# MA_board_1.net
KiCad netlist of a schematic drawn in EAGLE
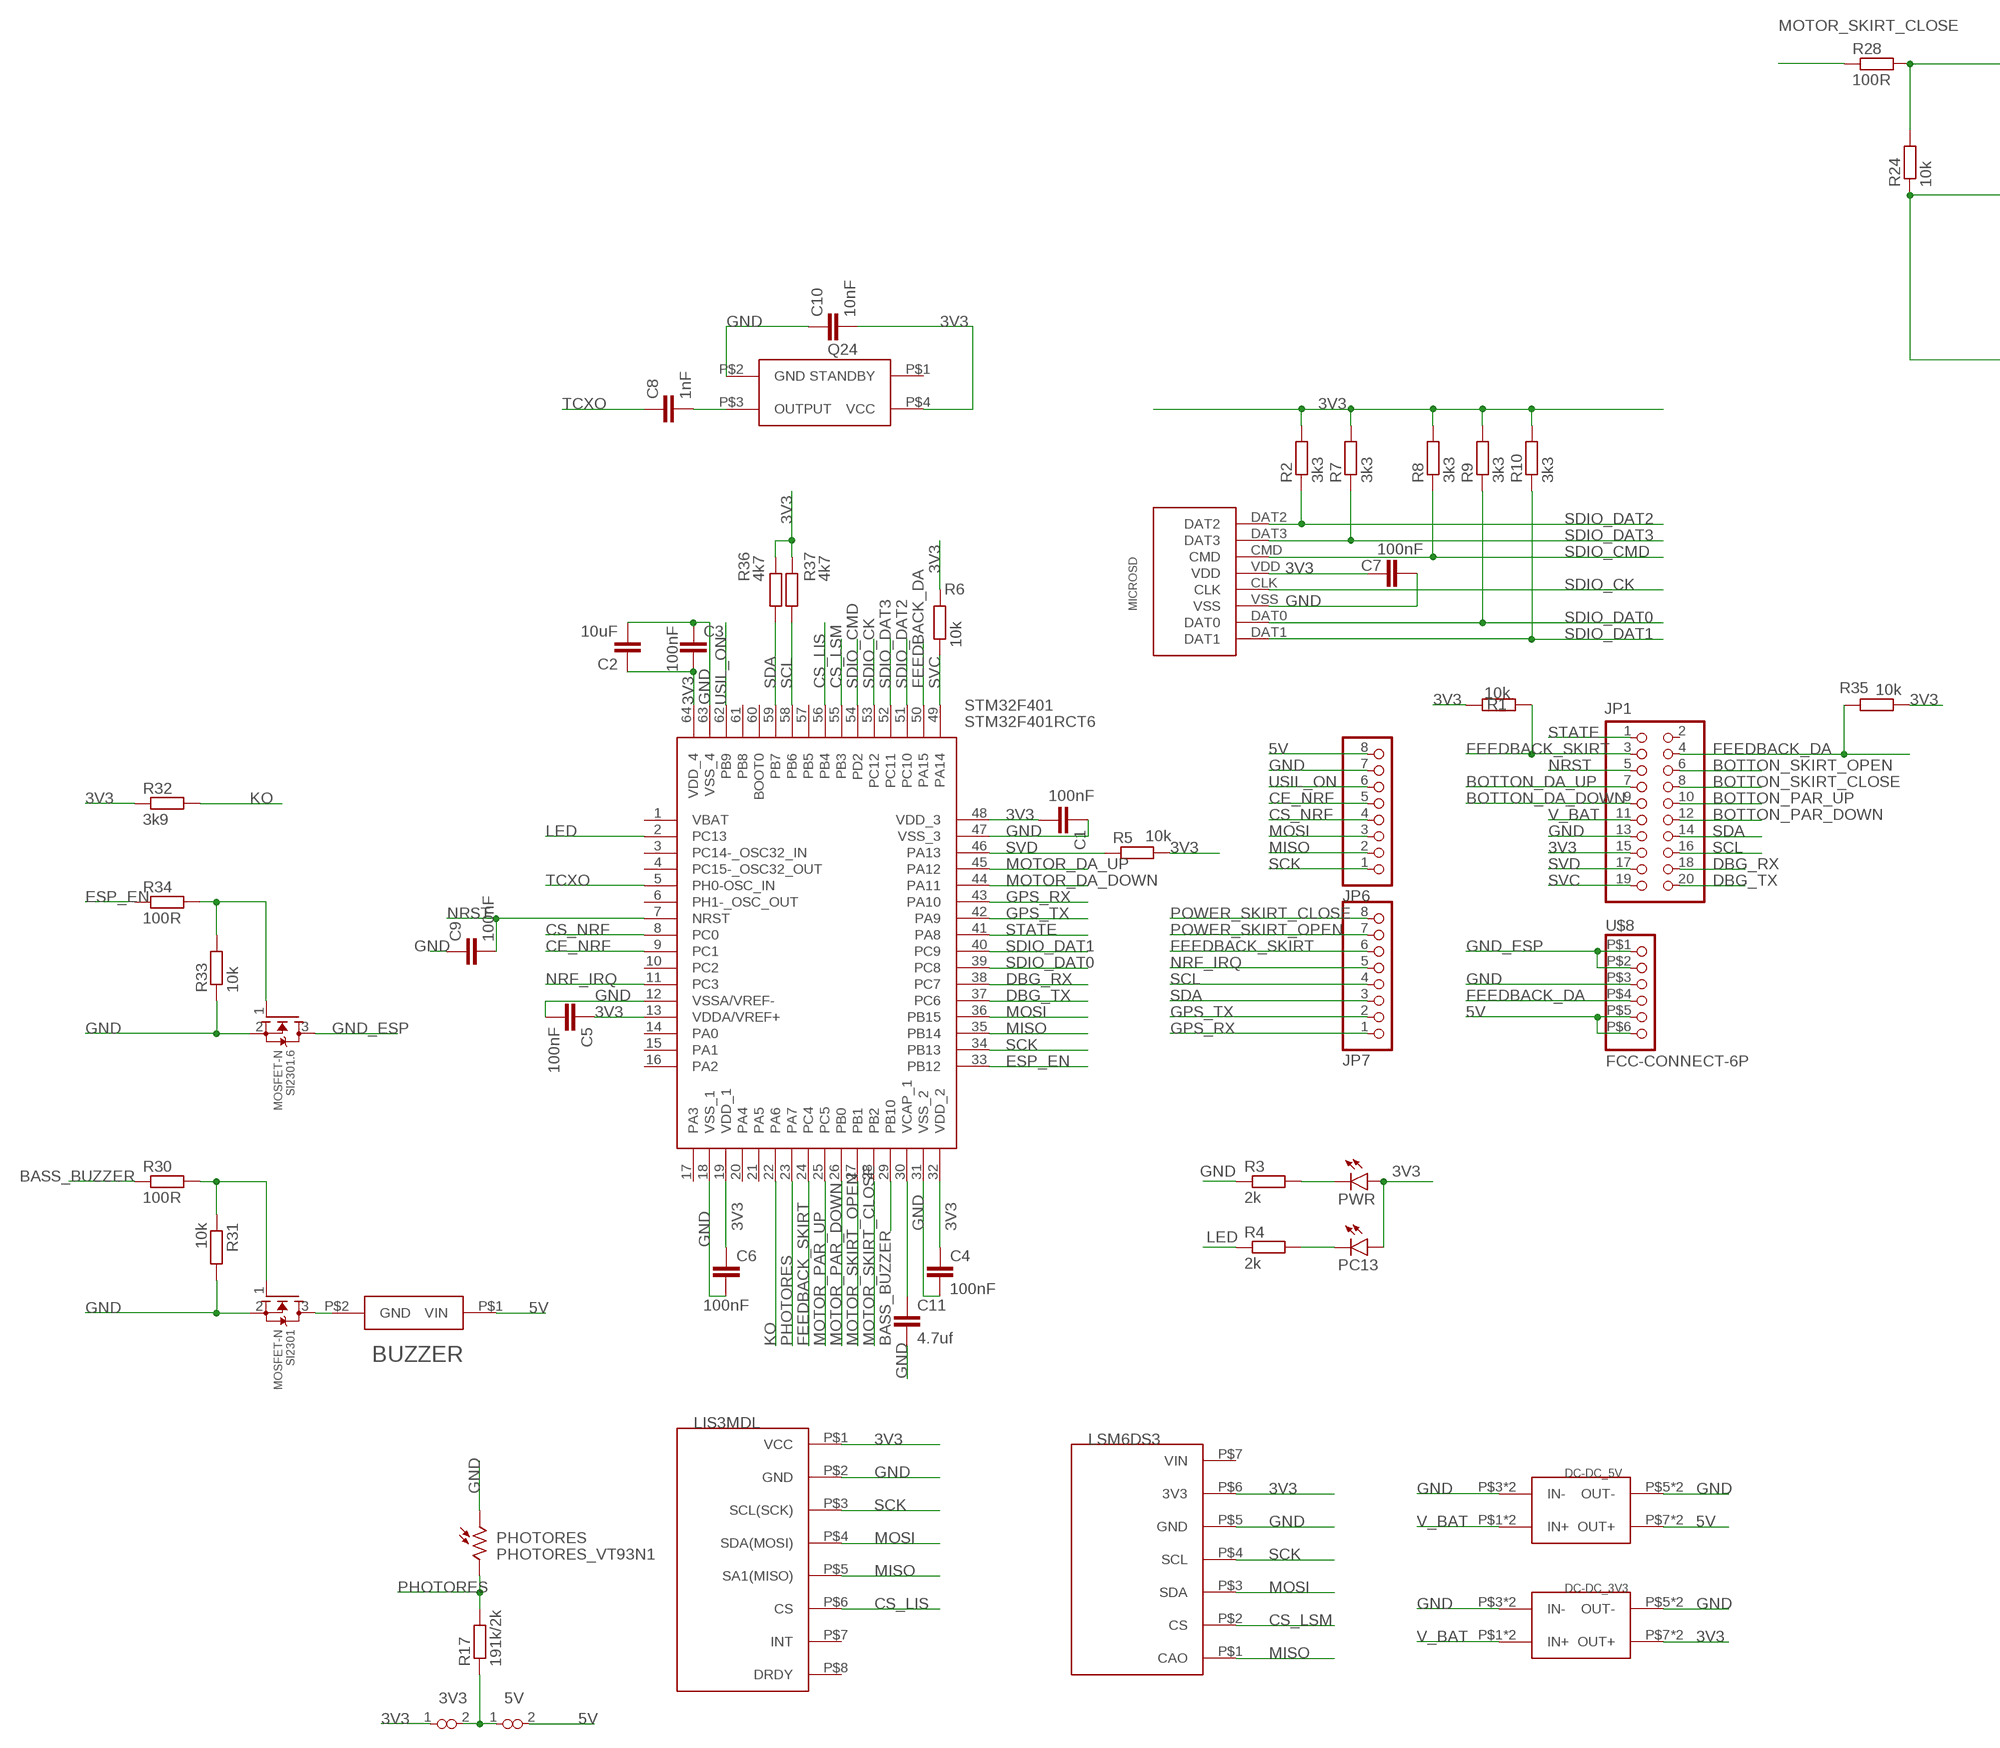
[diagram p0: schematic, sheet 1, part 1 of 2]
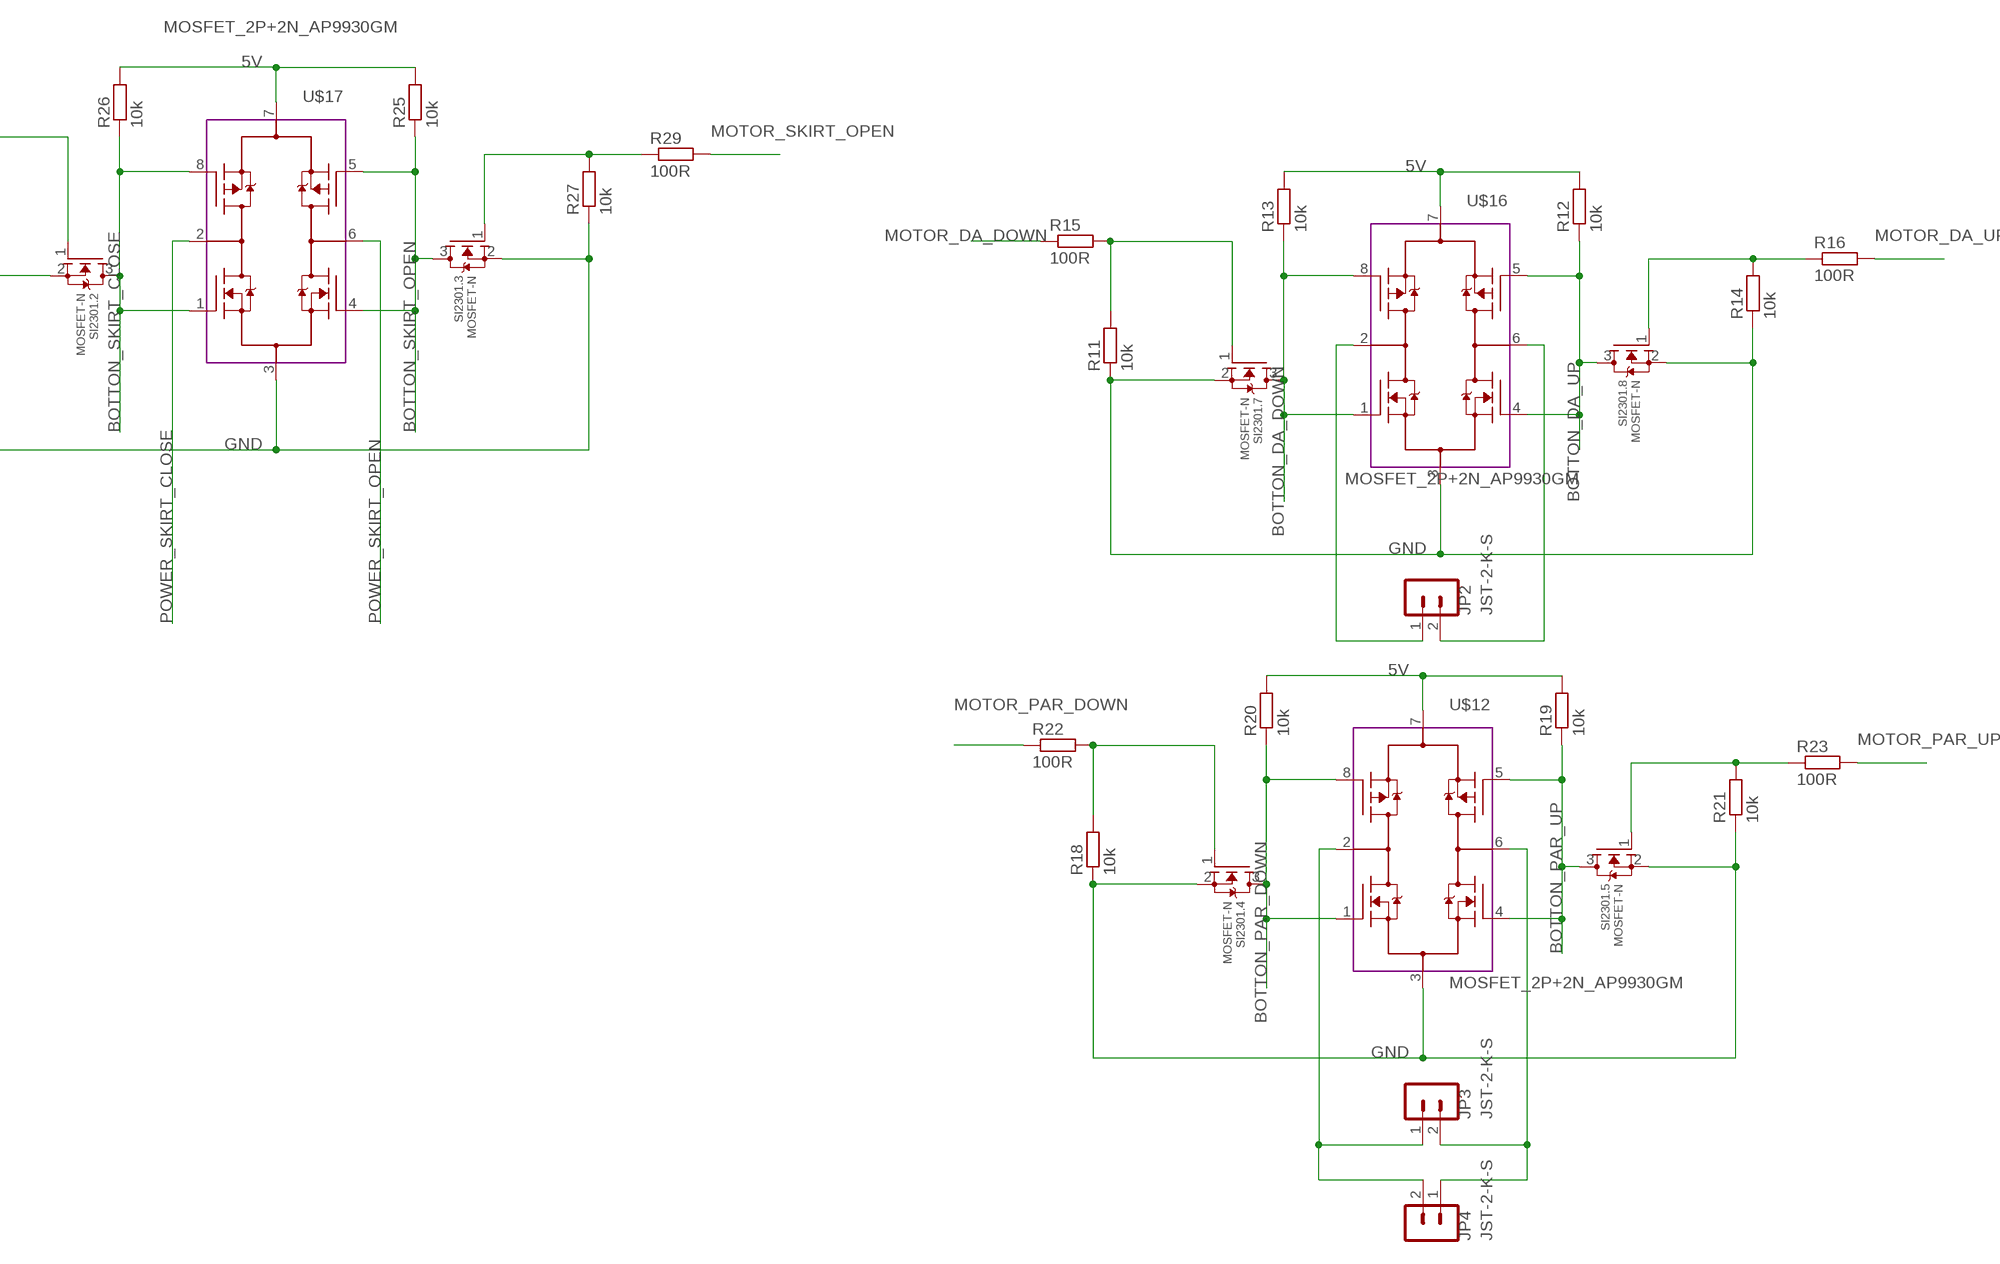
[diagram p1: schematic, sheet 1, part 2 of 2]

(export (version "E")
  (design (tool "Eeschema 10.0.6"))
  (components
    (comp (ref "3V3")
      (value "VIAS-CONNECT")
      (footprint "eagle-import:VIAS-CONNECT")
      (libsource (lib "eagle-import") (part "VIAS-CONNECT"))
    )
    (comp (ref "5V")
      (value "VIAS-CONNECT")
      (footprint "eagle-import:VIAS-CONNECT")
      (libsource (lib "eagle-import") (part "VIAS-CONNECT"))
    )
    (comp (ref "BUZZER")
      (value "BUZZERS8R6")
      (footprint "eagle-import:BUZZER-S8R12")
      (libsource (lib "eagle-import") (part "BUZZERS8R6"))
    )
    (comp (ref "C1")
      (value "100nF")
      (footprint "eagle-import:C0603")
      (libsource (lib "eagle-import") (part "C-EUC0603"))
    )
    (comp (ref "C2")
      (value "10uF")
      (footprint "eagle-import:C1206")
      (libsource (lib "eagle-import") (part "C-EUC1206"))
    )
    (comp (ref "C3")
      (value "100nF")
      (footprint "eagle-import:C0603")
      (libsource (lib "eagle-import") (part "C-EUC0603"))
    )
    (comp (ref "C4")
      (value "100nF")
      (footprint "eagle-import:C0603")
      (libsource (lib "eagle-import") (part "C-EUC0603"))
    )
    (comp (ref "C5")
      (value "100nF")
      (footprint "eagle-import:C0603")
      (libsource (lib "eagle-import") (part "C-EUC0603"))
    )
    (comp (ref "C6")
      (value "100nF")
      (footprint "eagle-import:C0603")
      (libsource (lib "eagle-import") (part "C-EUC0603"))
    )
    (comp (ref "C7")
      (value "100nF")
      (footprint "eagle-import:C0603")
      (libsource (lib "eagle-import") (part "C-EUC0603"))
    )
    (comp (ref "C8")
      (value "1nF")
      (footprint "eagle-import:C0603")
      (libsource (lib "eagle-import") (part "C-EUC0603"))
    )
    (comp (ref "C9")
      (value "100nF")
      (footprint "eagle-import:C0603")
      (libsource (lib "eagle-import") (part "C-EUC0603"))
    )
    (comp (ref "C10")
      (value "10nF")
      (footprint "eagle-import:C0603")
      (libsource (lib "eagle-import") (part "C-EUC0603"))
    )
    (comp (ref "C11")
      (value "4.7uf")
      (footprint "eagle-import:C0603")
      (libsource (lib "eagle-import") (part "C-EUC0603"))
    )
    (comp (ref "DC-DC_3V3")
      (value "MP1584-B")
      (footprint "eagle-import:MP1584-B")
      (libsource (lib "eagle-import") (part "MP1584-B"))
    )
    (comp (ref "DC-DC_5V")
      (value "MP1584-B")
      (footprint "eagle-import:MP1584-B")
      (libsource (lib "eagle-import") (part "MP1584-B"))
    )
    (comp (ref "JP1")
      (value "PINHD-2X10/90")
      (footprint "eagle-import:2X10_90")
      (libsource (lib "eagle-import") (part "PINHD-2X10/90"))
    )
    (comp (ref "JP2")
      (value "JST-2-K-S")
      (footprint "eagle-import:B2B-PH-K-S")
      (libsource (lib "eagle-import") (part "JST-2-K-S"))
    )
    (comp (ref "JP3")
      (value "JST-2-K-S")
      (footprint "eagle-import:B2B-PH-K-S")
      (libsource (lib "eagle-import") (part "JST-2-K-S"))
    )
    (comp (ref "JP4")
      (value "JST-2-K-S")
      (footprint "eagle-import:B2B-PH-K-S")
      (libsource (lib "eagle-import") (part "JST-2-K-S"))
    )
    (comp (ref "JP6")
      (value "PINHD-1X8-SHORT-PAD")
      (footprint "eagle-import:1X08")
      (libsource (lib "eagle-import") (part "PINHD-1X8-SHORT-PAD"))
    )
    (comp (ref "JP7")
      (value "PINHD-1X8-SHORT-PAD")
      (footprint "eagle-import:1X08")
      (libsource (lib "eagle-import") (part "PINHD-1X8-SHORT-PAD"))
    )
    (comp (ref "LIS3MDL")
      (value "LIS3MDL-CJMCUБез_отв._зеркальный")
      (footprint "eagle-import:LIS3MDL-CGMSU-NB2023")
      (libsource (lib "eagle-import") (part "LIS3MDL-CJMCUБез_отв._зеркальный"))
    )
    (comp (ref "LSM6DS3")
      (value "LSM6DS3-GY-NB2023")
      (footprint "eagle-import:LSM6DS3-GY-NB2023")
      (libsource (lib "eagle-import") (part "LSM6DS3-GY-NB2023"))
    )
    (comp (ref "MICROSD")
      (value "SD")
      (footprint "eagle-import:SD")
      (libsource (lib "eagle-import") (part "SD"))
    )
    (comp (ref "PC13")
      (value "LEDCHIPLED_0603")
      (footprint "eagle-import:CHIPLED_0603")
      (libsource (lib "eagle-import") (part "LEDCHIPLED_0603"))
    )
    (comp (ref "PHOTORES")
      (value "PHOTORES_VT93N1")
      (footprint "eagle-import:PHOTORES_VT93N1_SMD")
      (libsource (lib "eagle-import") (part "PHOTORES_VT93N1"))
    )
    (comp (ref "PWR")
      (value "LEDCHIPLED_0603")
      (footprint "eagle-import:CHIPLED_0603")
      (libsource (lib "eagle-import") (part "LEDCHIPLED_0603"))
    )
    (comp (ref "Q24")
      (value "Q24")
      (footprint "eagle-import:Q24")
      (libsource (lib "eagle-import") (part "Q24"))
    )
    (comp (ref "R1")
      (value "10k")
      (footprint "eagle-import:R0603")
      (libsource (lib "eagle-import") (part "R-EU_R0603"))
    )
    (comp (ref "R2")
      (value "3k3")
      (footprint "eagle-import:R0603")
      (libsource (lib "eagle-import") (part "R-EU_R0603"))
    )
    (comp (ref "R3")
      (value "2k")
      (footprint "eagle-import:R0603")
      (libsource (lib "eagle-import") (part "R-EU_R0603"))
    )
    (comp (ref "R4")
      (value "2k")
      (footprint "eagle-import:R0603")
      (libsource (lib "eagle-import") (part "R-EU_R0603"))
    )
    (comp (ref "R5")
      (value "10k")
      (footprint "eagle-import:R0603")
      (libsource (lib "eagle-import") (part "R-EU_R0603"))
    )
    (comp (ref "R6")
      (value "10k")
      (footprint "eagle-import:R0603")
      (libsource (lib "eagle-import") (part "R-EU_R0603"))
    )
    (comp (ref "R7")
      (value "3k3")
      (footprint "eagle-import:R0603")
      (libsource (lib "eagle-import") (part "R-EU_R0603"))
    )
    (comp (ref "R8")
      (value "3k3")
      (footprint "eagle-import:R0603")
      (libsource (lib "eagle-import") (part "R-EU_R0603"))
    )
    (comp (ref "R9")
      (value "3k3")
      (footprint "eagle-import:R0603")
      (libsource (lib "eagle-import") (part "R-EU_R0603"))
    )
    (comp (ref "R10")
      (value "3k3")
      (footprint "eagle-import:R0603")
      (libsource (lib "eagle-import") (part "R-EU_R0603"))
    )
    (comp (ref "R11")
      (value "10k")
      (footprint "eagle-import:R0603")
      (libsource (lib "eagle-import") (part "R-EU_R0603"))
    )
    (comp (ref "R12")
      (value "10k")
      (footprint "eagle-import:R0603")
      (libsource (lib "eagle-import") (part "R-EU_R0603"))
    )
    (comp (ref "R13")
      (value "10k")
      (footprint "eagle-import:R0603")
      (libsource (lib "eagle-import") (part "R-EU_R0603"))
    )
    (comp (ref "R14")
      (value "10k")
      (footprint "eagle-import:R0603")
      (libsource (lib "eagle-import") (part "R-EU_R0603"))
    )
    (comp (ref "R15")
      (value "100R")
      (footprint "eagle-import:R0603")
      (libsource (lib "eagle-import") (part "R-EU_R0603"))
    )
    (comp (ref "R16")
      (value "100R")
      (footprint "eagle-import:R0603")
      (libsource (lib "eagle-import") (part "R-EU_R0603"))
    )
    (comp (ref "R17")
      (value "191k/2k")
      (footprint "eagle-import:R0603")
      (libsource (lib "eagle-import") (part "R-EU_R0603"))
    )
    (comp (ref "R18")
      (value "10k")
      (footprint "eagle-import:R0603")
      (libsource (lib "eagle-import") (part "R-EU_R0603"))
    )
    (comp (ref "R19")
      (value "10k")
      (footprint "eagle-import:R0603")
      (libsource (lib "eagle-import") (part "R-EU_R0603"))
    )
    (comp (ref "R20")
      (value "10k")
      (footprint "eagle-import:R0603")
      (libsource (lib "eagle-import") (part "R-EU_R0603"))
    )
    (comp (ref "R21")
      (value "10k")
      (footprint "eagle-import:R0603")
      (libsource (lib "eagle-import") (part "R-EU_R0603"))
    )
    (comp (ref "R22")
      (value "100R")
      (footprint "eagle-import:R0603")
      (libsource (lib "eagle-import") (part "R-EU_R0603"))
    )
    (comp (ref "R23")
      (value "100R")
      (footprint "eagle-import:R0603")
      (libsource (lib "eagle-import") (part "R-EU_R0603"))
    )
    (comp (ref "R24")
      (value "10k")
      (footprint "eagle-import:R0603")
      (libsource (lib "eagle-import") (part "R-EU_R0603"))
    )
    (comp (ref "R25")
      (value "10k")
      (footprint "eagle-import:R0603")
      (libsource (lib "eagle-import") (part "R-EU_R0603"))
    )
    (comp (ref "R26")
      (value "10k")
      (footprint "eagle-import:R0603")
      (libsource (lib "eagle-import") (part "R-EU_R0603"))
    )
    (comp (ref "R27")
      (value "10k")
      (footprint "eagle-import:R0603")
      (libsource (lib "eagle-import") (part "R-EU_R0603"))
    )
    (comp (ref "R28")
      (value "100R")
      (footprint "eagle-import:R0603")
      (libsource (lib "eagle-import") (part "R-EU_R0603"))
    )
    (comp (ref "R29")
      (value "100R")
      (footprint "eagle-import:R0603")
      (libsource (lib "eagle-import") (part "R-EU_R0603"))
    )
    (comp (ref "R30")
      (value "100R")
      (footprint "eagle-import:R0603")
      (libsource (lib "eagle-import") (part "R-EU_R0603"))
    )
    (comp (ref "R31")
      (value "10k")
      (footprint "eagle-import:R0603")
      (libsource (lib "eagle-import") (part "R-EU_R0603"))
    )
    (comp (ref "R32")
      (value "3k9")
      (footprint "eagle-import:R0603")
      (libsource (lib "eagle-import") (part "R-EU_R0603"))
    )
    (comp (ref "R33")
      (value "10k")
      (footprint "eagle-import:R0603")
      (libsource (lib "eagle-import") (part "R-EU_R0603"))
    )
    (comp (ref "R34")
      (value "100R")
      (footprint "eagle-import:R0603")
      (libsource (lib "eagle-import") (part "R-EU_R0603"))
    )
    (comp (ref "R35")
      (value "10k")
      (footprint "eagle-import:R0603")
      (libsource (lib "eagle-import") (part "R-EU_R0603"))
    )
    (comp (ref "R36")
      (value "4k7")
      (footprint "eagle-import:R0603")
      (libsource (lib "eagle-import") (part "R-EU_R0603"))
    )
    (comp (ref "R37")
      (value "4k7")
      (footprint "eagle-import:R0603")
      (libsource (lib "eagle-import") (part "R-EU_R0603"))
    )
    (comp (ref "SI2301")
      (value "MOSFET-N")
      (footprint "eagle-import:SOT23-3")
      (libsource (lib "eagle-import") (part "MOSFET-N"))
    )
    (comp (ref "SI2301.2")
      (value "MOSFET-N")
      (footprint "eagle-import:SOT23-3")
      (libsource (lib "eagle-import") (part "MOSFET-N"))
    )
    (comp (ref "SI2301.3")
      (value "MOSFET-N")
      (footprint "eagle-import:SOT23-3")
      (libsource (lib "eagle-import") (part "MOSFET-N"))
    )
    (comp (ref "SI2301.4")
      (value "MOSFET-N")
      (footprint "eagle-import:SOT23-3")
      (libsource (lib "eagle-import") (part "MOSFET-N"))
    )
    (comp (ref "SI2301.5")
      (value "MOSFET-N")
      (footprint "eagle-import:SOT23-3")
      (libsource (lib "eagle-import") (part "MOSFET-N"))
    )
    (comp (ref "SI2301.6")
      (value "MOSFET-N")
      (footprint "eagle-import:SOT23-3")
      (libsource (lib "eagle-import") (part "MOSFET-N"))
    )
    (comp (ref "SI2301.7")
      (value "MOSFET-N")
      (footprint "eagle-import:SOT23-3")
      (libsource (lib "eagle-import") (part "MOSFET-N"))
    )
    (comp (ref "SI2301.8")
      (value "MOSFET-N")
      (footprint "eagle-import:SOT23-3")
      (libsource (lib "eagle-import") (part "MOSFET-N"))
    )
    (comp (ref "STM32F401")
      (value "STM32F401RCT6")
      (footprint "eagle-import:QFP50P1200X1200X160-64N")
      (fields (field (name "MOUSER_PART_NUMBER") "511-STM32F401RCT6"))
      (libsource (lib "eagle-import") (part "STM32F401RCT6"))
    )
    (comp (ref "U$8")
      (value "FCC-CONNECT-6P")
      (footprint "eagle-import:FFC-CONNECT-6P-SMD")
      (libsource (lib "eagle-import") (part "FCC-CONNECT-6P"))
    )
    (comp (ref "U$12")
      (value "MOSFET_2P+2N_AP9930GM")
      (footprint "eagle-import:SO8")
      (libsource (lib "eagle-import") (part "MOSFET_2P+2N_AP9930GM"))
    )
    (comp (ref "U$16")
      (value "MOSFET_2P+2N_AP9930GM")
      (footprint "eagle-import:SO8")
      (libsource (lib "eagle-import") (part "MOSFET_2P+2N_AP9930GM"))
    )
    (comp (ref "U$17")
      (value "MOSFET_2P+2N_AP9930GM")
      (footprint "eagle-import:SO8")
      (libsource (lib "eagle-import") (part "MOSFET_2P+2N_AP9930GM"))
    )
  )
  (nets
    (net (code "1") (name "/3V3") (class "Default")
      (node (ref "3V3") (pin "1") (pinfunction "1_1") (pintype "passive"))
      (node (ref "C1") (pin "2") (pinfunction "2_2") (pintype "passive"))
      (node (ref "C10") (pin "2") (pinfunction "2_2") (pintype "passive"))
      (node (ref "C2") (pin "1") (pinfunction "1_1") (pintype "passive"))
      (node (ref "C3") (pin "2") (pinfunction "2_2") (pintype "passive"))
      (node (ref "C4") (pin "1") (pinfunction "1_1") (pintype "passive"))
      (node (ref "C5") (pin "1") (pinfunction "1_1") (pintype "passive"))
      (node (ref "C6") (pin "1") (pinfunction "1_1") (pintype "passive"))
      (node (ref "C7") (pin "2") (pinfunction "2_2") (pintype "passive"))
      (node (ref "DC-DC_3V3") (pin "P$7") (pinfunction "OUT+_P$7") (pintype "bidirectional"))
      (node (ref "DC-DC_3V3") (pin "P$8") (pinfunction "OUT+_P$8") (pintype "bidirectional"))
      (node (ref "JP1") (pin "15") (pinfunction "15_15") (pintype "passive"))
      (node (ref "LIS3MDL") (pin "P$1") (pinfunction "VCC_P$1") (pintype "bidirectional"))
      (node (ref "LSM6DS3") (pin "P$6") (pinfunction "3V3_P$6") (pintype "bidirectional"))
      (node (ref "MICROSD") (pin "VDD") (pinfunction "VDD_VDD") (pintype "bidirectional"))
      (node (ref "PC13") (pin "A") (pinfunction "A_A") (pintype "passive"))
      (node (ref "PWR") (pin "A") (pinfunction "A_A") (pintype "passive"))
      (node (ref "Q24") (pin "P$4") (pinfunction "VCC_P$4") (pintype "bidirectional"))
      (node (ref "R1") (pin "2") (pinfunction "2_2") (pintype "passive"))
      (node (ref "R10") (pin "2") (pinfunction "2_2") (pintype "passive"))
      (node (ref "R2") (pin "2") (pinfunction "2_2") (pintype "passive"))
      (node (ref "R32") (pin "1") (pinfunction "1_1") (pintype "passive"))
      (node (ref "R35") (pin "1") (pinfunction "1_1") (pintype "passive"))
      (node (ref "R36") (pin "2") (pinfunction "2_2") (pintype "passive"))
      (node (ref "R37") (pin "2") (pinfunction "2_2") (pintype "passive"))
      (node (ref "R5") (pin "2") (pinfunction "2_2") (pintype "passive"))
      (node (ref "R6") (pin "2") (pinfunction "2_2") (pintype "passive"))
      (node (ref "R7") (pin "2") (pinfunction "2_2") (pintype "passive"))
      (node (ref "R8") (pin "2") (pinfunction "2_2") (pintype "passive"))
      (node (ref "R9") (pin "2") (pinfunction "2_2") (pintype "passive"))
      (node (ref "STM32F401") (pin "13") (pinfunction "VDDA/VREF+_13") (pintype "bidirectional"))
      (node (ref "STM32F401") (pin "19") (pinfunction "VDD_1_19") (pintype "bidirectional"))
      (node (ref "STM32F401") (pin "32") (pinfunction "VDD_2_32") (pintype "bidirectional"))
      (node (ref "STM32F401") (pin "48") (pinfunction "VDD_3_48") (pintype "bidirectional"))
      (node (ref "STM32F401") (pin "64") (pinfunction "VDD_4_64") (pintype "bidirectional"))
    )
    (net (code "2") (name "/5V") (class "Default")
      (node (ref "5V") (pin "2") (pinfunction "2_2") (pintype "passive"))
      (node (ref "BUZZER") (pin "P$1") (pinfunction "VIN_P$1") (pintype "bidirectional"))
      (node (ref "DC-DC_5V") (pin "P$7") (pinfunction "OUT+_P$7") (pintype "bidirectional"))
      (node (ref "DC-DC_5V") (pin "P$8") (pinfunction "OUT+_P$8") (pintype "bidirectional"))
      (node (ref "JP6") (pin "8") (pinfunction "8_8") (pintype "passive"))
      (node (ref "R12") (pin "2") (pinfunction "2_2") (pintype "passive"))
      (node (ref "R13") (pin "2") (pinfunction "2_2") (pintype "passive"))
      (node (ref "R19") (pin "2") (pinfunction "2_2") (pintype "passive"))
      (node (ref "R20") (pin "2") (pinfunction "2_2") (pintype "passive"))
      (node (ref "R25") (pin "2") (pinfunction "2_2") (pintype "passive"))
      (node (ref "R26") (pin "2") (pinfunction "2_2") (pintype "passive"))
      (node (ref "U$12") (pin "7") (pinfunction "P1P2S_7") (pintype "passive"))
      (node (ref "U$16") (pin "7") (pinfunction "P1P2S_7") (pintype "passive"))
      (node (ref "U$17") (pin "7") (pinfunction "P1P2S_7") (pintype "passive"))
      (node (ref "U$8") (pin "P$5") (pinfunction "5_P$5") (pintype "passive"))
      (node (ref "U$8") (pin "P$6") (pinfunction "6_P$6") (pintype "passive"))
    )
    (net (code "3") (name "/BASS_BUZZER") (class "Default")
      (node (ref "R30") (pin "1") (pinfunction "1_1") (pintype "passive"))
      (node (ref "STM32F401") (pin "29") (pinfunction "PB10_29") (pintype "bidirectional"))
    )
    (net (code "4") (name "/BOTTON_DA_DOWN") (class "Default")
      (node (ref "JP1") (pin "9") (pinfunction "9_9") (pintype "passive"))
      (node (ref "R13") (pin "1") (pinfunction "1_1") (pintype "passive"))
      (node (ref "SI2301.7") (pin "3") (pinfunction "D_3") (pintype "bidirectional"))
      (node (ref "U$16") (pin "1") (pinfunction "N1G_1") (pintype "passive"))
      (node (ref "U$16") (pin "8") (pinfunction "P1G_8") (pintype "passive"))
    )
    (net (code "5") (name "/BOTTON_DA_UP") (class "Default")
      (node (ref "JP1") (pin "7") (pinfunction "7_7") (pintype "passive"))
      (node (ref "R12") (pin "1") (pinfunction "1_1") (pintype "passive"))
      (node (ref "SI2301.8") (pin "3") (pinfunction "D_3") (pintype "bidirectional"))
      (node (ref "U$16") (pin "4") (pinfunction "N2G_4") (pintype "passive"))
      (node (ref "U$16") (pin "5") (pinfunction "P2G_5") (pintype "passive"))
    )
    (net (code "6") (name "/BOTTON_PAR_DOWN") (class "Default")
      (node (ref "JP1") (pin "12") (pinfunction "12_12") (pintype "passive"))
      (node (ref "R20") (pin "1") (pinfunction "1_1") (pintype "passive"))
      (node (ref "SI2301.4") (pin "3") (pinfunction "D_3") (pintype "bidirectional"))
      (node (ref "U$12") (pin "1") (pinfunction "N1G_1") (pintype "passive"))
      (node (ref "U$12") (pin "8") (pinfunction "P1G_8") (pintype "passive"))
    )
    (net (code "7") (name "/BOTTON_PAR_UP") (class "Default")
      (node (ref "JP1") (pin "10") (pinfunction "10_10") (pintype "passive"))
      (node (ref "R19") (pin "1") (pinfunction "1_1") (pintype "passive"))
      (node (ref "SI2301.5") (pin "3") (pinfunction "D_3") (pintype "bidirectional"))
      (node (ref "U$12") (pin "4") (pinfunction "N2G_4") (pintype "passive"))
      (node (ref "U$12") (pin "5") (pinfunction "P2G_5") (pintype "passive"))
    )
    (net (code "8") (name "/BOTTON_SKIRT_CLOSE") (class "Default")
      (node (ref "JP1") (pin "8") (pinfunction "8_8") (pintype "passive"))
      (node (ref "R26") (pin "1") (pinfunction "1_1") (pintype "passive"))
      (node (ref "SI2301.2") (pin "3") (pinfunction "D_3") (pintype "bidirectional"))
      (node (ref "U$17") (pin "1") (pinfunction "N1G_1") (pintype "passive"))
      (node (ref "U$17") (pin "8") (pinfunction "P1G_8") (pintype "passive"))
    )
    (net (code "9") (name "/BOTTON_SKIRT_OPEN") (class "Default")
      (node (ref "JP1") (pin "6") (pinfunction "6_6") (pintype "passive"))
      (node (ref "R25") (pin "1") (pinfunction "1_1") (pintype "passive"))
      (node (ref "SI2301.3") (pin "3") (pinfunction "D_3") (pintype "bidirectional"))
      (node (ref "U$17") (pin "4") (pinfunction "N2G_4") (pintype "passive"))
      (node (ref "U$17") (pin "5") (pinfunction "P2G_5") (pintype "passive"))
    )
    (net (code "10") (name "/CE_NRF") (class "Default")
      (node (ref "JP6") (pin "5") (pinfunction "5_5") (pintype "passive"))
      (node (ref "STM32F401") (pin "9") (pinfunction "PC1_9") (pintype "bidirectional"))
    )
    (net (code "11") (name "/CS_LIS") (class "Default")
      (node (ref "LIS3MDL") (pin "P$6") (pinfunction "CS_P$6") (pintype "bidirectional"))
      (node (ref "STM32F401") (pin "56") (pinfunction "PB4_56") (pintype "bidirectional"))
    )
    (net (code "12") (name "/CS_LSM") (class "Default")
      (node (ref "LSM6DS3") (pin "P$2") (pinfunction "CS_P$2") (pintype "bidirectional"))
      (node (ref "STM32F401") (pin "55") (pinfunction "PB3_55") (pintype "bidirectional"))
    )
    (net (code "13") (name "/CS_NRF") (class "Default")
      (node (ref "JP6") (pin "4") (pinfunction "4_4") (pintype "passive"))
      (node (ref "STM32F401") (pin "8") (pinfunction "PC0_8") (pintype "bidirectional"))
    )
    (net (code "14") (name "/DBG_RX") (class "Default")
      (node (ref "JP1") (pin "18") (pinfunction "18_18") (pintype "passive"))
      (node (ref "STM32F401") (pin "38") (pinfunction "PC7_38") (pintype "bidirectional"))
    )
    (net (code "15") (name "/DBG_TX") (class "Default")
      (node (ref "JP1") (pin "20") (pinfunction "20_20") (pintype "passive"))
      (node (ref "STM32F401") (pin "37") (pinfunction "PC6_37") (pintype "bidirectional"))
    )
    (net (code "16") (name "/ESP_EN") (class "Default")
      (node (ref "R34") (pin "1") (pinfunction "1_1") (pintype "passive"))
      (node (ref "STM32F401") (pin "33") (pinfunction "PB12_33") (pintype "bidirectional"))
    )
    (net (code "17") (name "/FEEDBACK_DA") (class "Default")
      (node (ref "JP1") (pin "4") (pinfunction "4_4") (pintype "passive"))
      (node (ref "R35") (pin "2") (pinfunction "2_2") (pintype "passive"))
      (node (ref "STM32F401") (pin "50") (pinfunction "PA15_50") (pintype "bidirectional"))
      (node (ref "U$8") (pin "P$4") (pinfunction "4_P$4") (pintype "passive"))
    )
    (net (code "18") (name "/FEEDBACK_SKIRT") (class "Default")
      (node (ref "JP1") (pin "3") (pinfunction "3_3") (pintype "passive"))
      (node (ref "JP7") (pin "6") (pinfunction "6_6") (pintype "passive"))
      (node (ref "R1") (pin "1") (pinfunction "1_1") (pintype "passive"))
      (node (ref "STM32F401") (pin "24") (pinfunction "PC4_24") (pintype "bidirectional"))
    )
    (net (code "19") (name "/GND") (class "Default")
      (node (ref "C1") (pin "1") (pinfunction "1_1") (pintype "passive"))
      (node (ref "C10") (pin "1") (pinfunction "1_1") (pintype "passive"))
      (node (ref "C11") (pin "2") (pinfunction "2_2") (pintype "passive"))
      (node (ref "C2") (pin "2") (pinfunction "2_2") (pintype "passive"))
      (node (ref "C3") (pin "1") (pinfunction "1_1") (pintype "passive"))
      (node (ref "C4") (pin "2") (pinfunction "2_2") (pintype "passive"))
      (node (ref "C5") (pin "2") (pinfunction "2_2") (pintype "passive"))
      (node (ref "C6") (pin "2") (pinfunction "2_2") (pintype "passive"))
      (node (ref "C7") (pin "1") (pinfunction "1_1") (pintype "passive"))
      (node (ref "C9") (pin "1") (pinfunction "1_1") (pintype "passive"))
      (node (ref "DC-DC_3V3") (pin "P$3") (pinfunction "IN-_P$3") (pintype "bidirectional"))
      (node (ref "DC-DC_3V3") (pin "P$4") (pinfunction "IN-_P$4") (pintype "bidirectional"))
      (node (ref "DC-DC_3V3") (pin "P$5") (pinfunction "OUT-_P$5") (pintype "bidirectional"))
      (node (ref "DC-DC_3V3") (pin "P$6") (pinfunction "OUT-_P$6") (pintype "bidirectional"))
      (node (ref "DC-DC_5V") (pin "P$3") (pinfunction "IN-_P$3") (pintype "bidirectional"))
      (node (ref "DC-DC_5V") (pin "P$4") (pinfunction "IN-_P$4") (pintype "bidirectional"))
      (node (ref "DC-DC_5V") (pin "P$5") (pinfunction "OUT-_P$5") (pintype "bidirectional"))
      (node (ref "DC-DC_5V") (pin "P$6") (pinfunction "OUT-_P$6") (pintype "bidirectional"))
      (node (ref "JP1") (pin "13") (pinfunction "13_13") (pintype "passive"))
      (node (ref "JP6") (pin "7") (pinfunction "7_7") (pintype "passive"))
      (node (ref "LIS3MDL") (pin "P$2") (pinfunction "GND_P$2") (pintype "bidirectional"))
      (node (ref "LSM6DS3") (pin "P$5") (pinfunction "GND_P$5") (pintype "bidirectional"))
      (node (ref "MICROSD") (pin "VSS") (pinfunction "VSS_VSS") (pintype "bidirectional"))
      (node (ref "PHOTORES") (pin "P$1") (pinfunction "1_P$1") (pintype "passive"))
      (node (ref "Q24") (pin "P$2") (pinfunction "GND_P$2") (pintype "bidirectional"))
      (node (ref "R11") (pin "1") (pinfunction "1_1") (pintype "passive"))
      (node (ref "R14") (pin "1") (pinfunction "1_1") (pintype "passive"))
      (node (ref "R18") (pin "1") (pinfunction "1_1") (pintype "passive"))
      (node (ref "R21") (pin "1") (pinfunction "1_1") (pintype "passive"))
      (node (ref "R24") (pin "1") (pinfunction "1_1") (pintype "passive"))
      (node (ref "R27") (pin "1") (pinfunction "1_1") (pintype "passive"))
      (node (ref "R3") (pin "1") (pinfunction "1_1") (pintype "passive"))
      (node (ref "R31") (pin "2") (pinfunction "2_2") (pintype "passive"))
      (node (ref "R33") (pin "1") (pinfunction "1_1") (pintype "passive"))
      (node (ref "SI2301") (pin "2") (pinfunction "S_2") (pintype "bidirectional"))
      (node (ref "SI2301.2") (pin "2") (pinfunction "S_2") (pintype "bidirectional"))
      (node (ref "SI2301.3") (pin "2") (pinfunction "S_2") (pintype "bidirectional"))
      (node (ref "SI2301.4") (pin "2") (pinfunction "S_2") (pintype "bidirectional"))
      (node (ref "SI2301.5") (pin "2") (pinfunction "S_2") (pintype "bidirectional"))
      (node (ref "SI2301.6") (pin "2") (pinfunction "S_2") (pintype "bidirectional"))
      (node (ref "SI2301.7") (pin "2") (pinfunction "S_2") (pintype "bidirectional"))
      (node (ref "SI2301.8") (pin "2") (pinfunction "S_2") (pintype "bidirectional"))
      (node (ref "STM32F401") (pin "12") (pinfunction "VSSA/VREF-_12") (pintype "bidirectional"))
      (node (ref "STM32F401") (pin "18") (pinfunction "VSS_1_18") (pintype "bidirectional"))
      (node (ref "STM32F401") (pin "31") (pinfunction "VSS_2_31") (pintype "bidirectional"))
      (node (ref "STM32F401") (pin "47") (pinfunction "VSS_3_47") (pintype "bidirectional"))
      (node (ref "STM32F401") (pin "63") (pinfunction "VSS_4_63") (pintype "bidirectional"))
      (node (ref "U$12") (pin "3") (pinfunction "N1N2S_3") (pintype "passive"))
      (node (ref "U$16") (pin "3") (pinfunction "N1N2S_3") (pintype "passive"))
      (node (ref "U$17") (pin "3") (pinfunction "N1N2S_3") (pintype "passive"))
      (node (ref "U$8") (pin "P$3") (pinfunction "3_P$3") (pintype "passive"))
    )
    (net (code "20") (name "/GND_ESP") (class "Default")
      (node (ref "SI2301.6") (pin "3") (pinfunction "D_3") (pintype "bidirectional"))
      (node (ref "U$8") (pin "P$1") (pinfunction "1_P$1") (pintype "passive"))
      (node (ref "U$8") (pin "P$2") (pinfunction "2_P$2") (pintype "passive"))
    )
    (net (code "21") (name "/GPS_RX") (class "Default")
      (node (ref "JP7") (pin "1") (pinfunction "1_1") (pintype "passive"))
      (node (ref "STM32F401") (pin "43") (pinfunction "PA10_43") (pintype "bidirectional"))
    )
    (net (code "22") (name "/GPS_TX") (class "Default")
      (node (ref "JP7") (pin "2") (pinfunction "2_2") (pintype "passive"))
      (node (ref "STM32F401") (pin "42") (pinfunction "PA9_42") (pintype "bidirectional"))
    )
    (net (code "23") (name "/KO") (class "Default")
      (node (ref "R32") (pin "2") (pinfunction "2_2") (pintype "passive"))
      (node (ref "STM32F401") (pin "22") (pinfunction "PA6_22") (pintype "bidirectional"))
    )
    (net (code "24") (name "/LED") (class "Default")
      (node (ref "R4") (pin "1") (pinfunction "1_1") (pintype "passive"))
      (node (ref "STM32F401") (pin "2") (pinfunction "PC13_2") (pintype "bidirectional"))
    )
    (net (code "25") (name "/MISO") (class "Default")
      (node (ref "JP6") (pin "2") (pinfunction "2_2") (pintype "passive"))
      (node (ref "LIS3MDL") (pin "P$5") (pinfunction "SA1(MISO)_P$5") (pintype "bidirectional"))
      (node (ref "LSM6DS3") (pin "P$1") (pinfunction "CAO_P$1") (pintype "bidirectional"))
      (node (ref "STM32F401") (pin "35") (pinfunction "PB14_35") (pintype "bidirectional"))
    )
    (net (code "26") (name "/MOSI") (class "Default")
      (node (ref "JP6") (pin "3") (pinfunction "3_3") (pintype "passive"))
      (node (ref "LIS3MDL") (pin "P$4") (pinfunction "SDA(MOSI)_P$4") (pintype "bidirectional"))
      (node (ref "LSM6DS3") (pin "P$3") (pinfunction "SDA_P$3") (pintype "bidirectional"))
      (node (ref "STM32F401") (pin "36") (pinfunction "PB15_36") (pintype "bidirectional"))
    )
    (net (code "27") (name "/MOTOR_DA_DOWN") (class "Default")
      (node (ref "R15") (pin "1") (pinfunction "1_1") (pintype "passive"))
      (node (ref "STM32F401") (pin "44") (pinfunction "PA11_44") (pintype "bidirectional"))
    )
    (net (code "28") (name "/MOTOR_DA_UP") (class "Default")
      (node (ref "R16") (pin "2") (pinfunction "2_2") (pintype "passive"))
      (node (ref "STM32F401") (pin "45") (pinfunction "PA12_45") (pintype "bidirectional"))
    )
    (net (code "29") (name "/MOTOR_PAR_DOWN") (class "Default")
      (node (ref "R22") (pin "1") (pinfunction "1_1") (pintype "passive"))
      (node (ref "STM32F401") (pin "26") (pinfunction "PB0_26") (pintype "bidirectional"))
    )
    (net (code "30") (name "/MOTOR_PAR_UP") (class "Default")
      (node (ref "R23") (pin "2") (pinfunction "2_2") (pintype "passive"))
      (node (ref "STM32F401") (pin "25") (pinfunction "PC5_25") (pintype "bidirectional"))
    )
    (net (code "31") (name "/MOTOR_SKIRT_CLOSE") (class "Default")
      (node (ref "R28") (pin "1") (pinfunction "1_1") (pintype "passive"))
      (node (ref "STM32F401") (pin "28") (pinfunction "PB2_28") (pintype "bidirectional"))
    )
    (net (code "32") (name "/MOTOR_SKIRT_OPEN") (class "Default")
      (node (ref "R29") (pin "2") (pinfunction "2_2") (pintype "passive"))
      (node (ref "STM32F401") (pin "27") (pinfunction "PB1_27") (pintype "bidirectional"))
    )
    (net (code "33") (name "/NRF_IRQ") (class "Default")
      (node (ref "JP7") (pin "5") (pinfunction "5_5") (pintype "passive"))
      (node (ref "STM32F401") (pin "11") (pinfunction "PC3_11") (pintype "bidirectional"))
    )
    (net (code "34") (name "/NRST") (class "Default")
      (node (ref "C9") (pin "2") (pinfunction "2_2") (pintype "passive"))
      (node (ref "JP1") (pin "5") (pinfunction "5_5") (pintype "passive"))
      (node (ref "STM32F401") (pin "7") (pinfunction "NRST_7") (pintype "bidirectional"))
    )
    (net (code "35") (name "/PHOTORES") (class "Default")
      (node (ref "PHOTORES") (pin "P$2") (pinfunction "2_P$2") (pintype "passive"))
      (node (ref "R17") (pin "2") (pinfunction "2_2") (pintype "passive"))
      (node (ref "STM32F401") (pin "23") (pinfunction "PA7_23") (pintype "bidirectional"))
    )
    (net (code "36") (name "/POWER_SKIRT_CLOSE") (class "Default")
      (node (ref "JP7") (pin "8") (pinfunction "8_8") (pintype "passive"))
      (node (ref "U$17") (pin "2") (pinfunction "P1N1D_2") (pintype "passive"))
    )
    (net (code "37") (name "/POWER_SKIRT_OPEN") (class "Default")
      (node (ref "JP7") (pin "7") (pinfunction "7_7") (pintype "passive"))
      (node (ref "U$17") (pin "6") (pinfunction "P2N2D_6") (pintype "passive"))
    )
    (net (code "38") (name "/SCK") (class "Default")
      (node (ref "JP6") (pin "1") (pinfunction "1_1") (pintype "passive"))
      (node (ref "LIS3MDL") (pin "P$3") (pinfunction "SCL(SCK)_P$3") (pintype "bidirectional"))
      (node (ref "LSM6DS3") (pin "P$4") (pinfunction "SCL_P$4") (pintype "bidirectional"))
      (node (ref "STM32F401") (pin "34") (pinfunction "PB13_34") (pintype "bidirectional"))
    )
    (net (code "39") (name "/SCL") (class "Default")
      (node (ref "JP1") (pin "16") (pinfunction "16_16") (pintype "passive"))
      (node (ref "JP7") (pin "4") (pinfunction "4_4") (pintype "passive"))
      (node (ref "R37") (pin "1") (pinfunction "1_1") (pintype "passive"))
      (node (ref "STM32F401") (pin "58") (pinfunction "PB6_58") (pintype "bidirectional"))
    )
    (net (code "40") (name "/SDA") (class "Default")
      (node (ref "JP1") (pin "14") (pinfunction "14_14") (pintype "passive"))
      (node (ref "JP7") (pin "3") (pinfunction "3_3") (pintype "passive"))
      (node (ref "R36") (pin "1") (pinfunction "1_1") (pintype "passive"))
      (node (ref "STM32F401") (pin "59") (pinfunction "PB7_59") (pintype "bidirectional"))
    )
    (net (code "41") (name "/SDIO_CK") (class "Default")
      (node (ref "MICROSD") (pin "CLK") (pinfunction "CLK_CLK") (pintype "bidirectional"))
      (node (ref "STM32F401") (pin "53") (pinfunction "PC12_53") (pintype "bidirectional"))
    )
    (net (code "42") (name "/SDIO_CMD") (class "Default")
      (node (ref "MICROSD") (pin "CMD") (pinfunction "CMD_CMD") (pintype "bidirectional"))
      (node (ref "R8") (pin "1") (pinfunction "1_1") (pintype "passive"))
      (node (ref "STM32F401") (pin "54") (pinfunction "PD2_54") (pintype "bidirectional"))
    )
    (net (code "43") (name "/SDIO_DAT0") (class "Default")
      (node (ref "MICROSD") (pin "DAT0") (pinfunction "DAT0_DAT0") (pintype "bidirectional"))
      (node (ref "R9") (pin "1") (pinfunction "1_1") (pintype "passive"))
      (node (ref "STM32F401") (pin "39") (pinfunction "PC8_39") (pintype "bidirectional"))
    )
    (net (code "44") (name "/SDIO_DAT1") (class "Default")
      (node (ref "MICROSD") (pin "DAT1") (pinfunction "DAT1_DAT1") (pintype "bidirectional"))
      (node (ref "R10") (pin "1") (pinfunction "1_1") (pintype "passive"))
      (node (ref "STM32F401") (pin "40") (pinfunction "PC9_40") (pintype "bidirectional"))
    )
    (net (code "45") (name "/SDIO_DAT2") (class "Default")
      (node (ref "MICROSD") (pin "DAT2") (pinfunction "DAT2_DAT2") (pintype "bidirectional"))
      (node (ref "R2") (pin "1") (pinfunction "1_1") (pintype "passive"))
      (node (ref "STM32F401") (pin "51") (pinfunction "PC10_51") (pintype "bidirectional"))
    )
    (net (code "46") (name "/SDIO_DAT3") (class "Default")
      (node (ref "MICROSD") (pin "DAT3") (pinfunction "DAT3_DAT3") (pintype "bidirectional"))
      (node (ref "R7") (pin "1") (pinfunction "1_1") (pintype "passive"))
      (node (ref "STM32F401") (pin "52") (pinfunction "PC11_52") (pintype "bidirectional"))
    )
    (net (code "47") (name "/STATE") (class "Default")
      (node (ref "JP1") (pin "1") (pinfunction "1_1") (pintype "passive"))
      (node (ref "STM32F401") (pin "41") (pinfunction "PA8_41") (pintype "bidirectional"))
    )
    (net (code "48") (name "/SVC") (class "Default")
      (node (ref "JP1") (pin "19") (pinfunction "19_19") (pintype "passive"))
      (node (ref "R6") (pin "1") (pinfunction "1_1") (pintype "passive"))
      (node (ref "STM32F401") (pin "49") (pinfunction "PA14_49") (pintype "bidirectional"))
    )
    (net (code "49") (name "/SVD") (class "Default")
      (node (ref "JP1") (pin "17") (pinfunction "17_17") (pintype "passive"))
      (node (ref "R5") (pin "1") (pinfunction "1_1") (pintype "passive"))
      (node (ref "STM32F401") (pin "46") (pinfunction "PA13_46") (pintype "bidirectional"))
    )
    (net (code "50") (name "/TCXO") (class "Default")
      (node (ref "C8") (pin "1") (pinfunction "1_1") (pintype "passive"))
      (node (ref "STM32F401") (pin "5") (pinfunction "PH0-OSC_IN_5") (pintype "bidirectional"))
    )
    (net (code "51") (name "/USIL_ON") (class "Default")
      (node (ref "JP6") (pin "6") (pinfunction "6_6") (pintype "passive"))
      (node (ref "STM32F401") (pin "62") (pinfunction "PB9_62") (pintype "bidirectional"))
    )
    (net (code "52") (name "/V_BAT") (class "Default")
      (node (ref "DC-DC_3V3") (pin "P$1") (pinfunction "IN+_P$1") (pintype "bidirectional"))
      (node (ref "DC-DC_3V3") (pin "P$2") (pinfunction "IN+_P$2") (pintype "bidirectional"))
      (node (ref "DC-DC_5V") (pin "P$1") (pinfunction "IN+_P$1") (pintype "bidirectional"))
      (node (ref "DC-DC_5V") (pin "P$2") (pinfunction "IN+_P$2") (pintype "bidirectional"))
      (node (ref "JP1") (pin "11") (pinfunction "11_11") (pintype "passive"))
    )
    (net (code "53") (name "Net-(3V3-Pad2)") (class "Default")
      (node (ref "3V3") (pin "2") (pinfunction "2_2") (pintype "passive"))
      (node (ref "5V") (pin "1") (pinfunction "1_1") (pintype "passive"))
      (node (ref "R17") (pin "1") (pinfunction "1_1") (pintype "passive"))
    )
    (net (code "54") (name "Net-(BUZZER-GND)") (class "Default")
      (node (ref "BUZZER") (pin "P$2") (pinfunction "GND_P$2") (pintype "bidirectional"))
      (node (ref "SI2301") (pin "3") (pinfunction "D_3") (pintype "bidirectional"))
    )
    (net (code "55") (name "Net-(PC13-PadC)") (class "Default")
      (node (ref "PC13") (pin "C") (pinfunction "C_C") (pintype "passive"))
      (node (ref "R4") (pin "2") (pinfunction "2_2") (pintype "passive"))
    )
    (net (code "56") (name "Net-(PWR-PadC)") (class "Default")
      (node (ref "PWR") (pin "C") (pinfunction "C_C") (pintype "passive"))
      (node (ref "R3") (pin "2") (pinfunction "2_2") (pintype "passive"))
    )
    (net (code "57") (name "Net-(Q24-OUTPUT)") (class "Default")
      (node (ref "C8") (pin "2") (pinfunction "2_2") (pintype "passive"))
      (node (ref "Q24") (pin "P$3") (pinfunction "OUTPUT_P$3") (pintype "bidirectional"))
    )
    (net (code "58") (name "Net-(SI2301-G)") (class "Default")
      (node (ref "R30") (pin "2") (pinfunction "2_2") (pintype "passive"))
      (node (ref "R31") (pin "1") (pinfunction "1_1") (pintype "passive"))
      (node (ref "SI2301") (pin "1") (pinfunction "G_1") (pintype "bidirectional"))
    )
    (net (code "59") (name "Net-(SI2301.2-G)") (class "Default")
      (node (ref "R24") (pin "2") (pinfunction "2_2") (pintype "passive"))
      (node (ref "R28") (pin "2") (pinfunction "2_2") (pintype "passive"))
      (node (ref "SI2301.2") (pin "1") (pinfunction "G_1") (pintype "bidirectional"))
    )
    (net (code "60") (name "Net-(SI2301.3-G)") (class "Default")
      (node (ref "R27") (pin "2") (pinfunction "2_2") (pintype "passive"))
      (node (ref "R29") (pin "1") (pinfunction "1_1") (pintype "passive"))
      (node (ref "SI2301.3") (pin "1") (pinfunction "G_1") (pintype "bidirectional"))
    )
    (net (code "61") (name "Net-(SI2301.4-G)") (class "Default")
      (node (ref "R18") (pin "2") (pinfunction "2_2") (pintype "passive"))
      (node (ref "R22") (pin "2") (pinfunction "2_2") (pintype "passive"))
      (node (ref "SI2301.4") (pin "1") (pinfunction "G_1") (pintype "bidirectional"))
    )
    (net (code "62") (name "Net-(SI2301.5-G)") (class "Default")
      (node (ref "R21") (pin "2") (pinfunction "2_2") (pintype "passive"))
      (node (ref "R23") (pin "1") (pinfunction "1_1") (pintype "passive"))
      (node (ref "SI2301.5") (pin "1") (pinfunction "G_1") (pintype "bidirectional"))
    )
    (net (code "63") (name "Net-(SI2301.6-G)") (class "Default")
      (node (ref "R33") (pin "2") (pinfunction "2_2") (pintype "passive"))
      (node (ref "R34") (pin "2") (pinfunction "2_2") (pintype "passive"))
      (node (ref "SI2301.6") (pin "1") (pinfunction "G_1") (pintype "bidirectional"))
    )
    (net (code "64") (name "Net-(SI2301.7-G)") (class "Default")
      (node (ref "R11") (pin "2") (pinfunction "2_2") (pintype "passive"))
      (node (ref "R15") (pin "2") (pinfunction "2_2") (pintype "passive"))
      (node (ref "SI2301.7") (pin "1") (pinfunction "G_1") (pintype "bidirectional"))
    )
    (net (code "65") (name "Net-(SI2301.8-G)") (class "Default")
      (node (ref "R14") (pin "2") (pinfunction "2_2") (pintype "passive"))
      (node (ref "R16") (pin "1") (pinfunction "1_1") (pintype "passive"))
      (node (ref "SI2301.8") (pin "1") (pinfunction "G_1") (pintype "bidirectional"))
    )
    (net (code "66") (name "Net-(STM32F401-VCAP_1)") (class "Default")
      (node (ref "C11") (pin "1") (pinfunction "1_1") (pintype "passive"))
      (node (ref "STM32F401") (pin "30") (pinfunction "VCAP_1_30") (pintype "bidirectional"))
    )
    (net (code "67") (name "Net-(U$12-P1N1D)") (class "Default")
      (node (ref "JP3") (pin "1") (pinfunction "1_1") (pintype "passive"))
      (node (ref "JP4") (pin "2") (pinfunction "2_2") (pintype "passive"))
      (node (ref "U$12") (pin "2") (pinfunction "P1N1D_2") (pintype "passive"))
    )
    (net (code "68") (name "Net-(U$12-P2N2D)") (class "Default")
      (node (ref "JP3") (pin "2") (pinfunction "2_2") (pintype "passive"))
      (node (ref "JP4") (pin "1") (pinfunction "1_1") (pintype "passive"))
      (node (ref "U$12") (pin "6") (pinfunction "P2N2D_6") (pintype "passive"))
    )
    (net (code "69") (name "Net-(U$16-P1N1D)") (class "Default")
      (node (ref "JP2") (pin "1") (pinfunction "1_1") (pintype "passive"))
      (node (ref "U$16") (pin "2") (pinfunction "P1N1D_2") (pintype "passive"))
    )
    (net (code "70") (name "Net-(U$16-P2N2D)") (class "Default")
      (node (ref "JP2") (pin "2") (pinfunction "2_2") (pintype "passive"))
      (node (ref "U$16") (pin "6") (pinfunction "P2N2D_6") (pintype "passive"))
    )
    (net (code "71") (name "unconnected-(JP1-Pad2)") (class "Default")
      (node (ref "JP1") (pin "2") (pinfunction "2_2") (pintype "passive"))
    )
    (net (code "72") (name "unconnected-(LIS3MDL-DRDY-PadP$8)") (class "Default")
      (node (ref "LIS3MDL") (pin "P$8") (pinfunction "DRDY_P$8") (pintype "bidirectional"))
    )
    (net (code "73") (name "unconnected-(LIS3MDL-INT-PadP$7)") (class "Default")
      (node (ref "LIS3MDL") (pin "P$7") (pinfunction "INT_P$7") (pintype "bidirectional"))
    )
    (net (code "74") (name "unconnected-(LSM6DS3-VIN-PadP$7)") (class "Default")
      (node (ref "LSM6DS3") (pin "P$7") (pinfunction "VIN_P$7") (pintype "bidirectional"))
    )
    (net (code "75") (name "unconnected-(Q24-STANDBY-PadP$1)") (class "Default")
      (node (ref "Q24") (pin "P$1") (pinfunction "STANDBY_P$1") (pintype "bidirectional"))
    )
    (net (code "76") (name "unconnected-(STM32F401-BOOT0-Pad60)") (class "Default")
      (node (ref "STM32F401") (pin "60") (pinfunction "BOOT0_60") (pintype "bidirectional"))
    )
    (net (code "77") (name "unconnected-(STM32F401-PA0-Pad14)") (class "Default")
      (node (ref "STM32F401") (pin "14") (pinfunction "PA0_14") (pintype "bidirectional"))
    )
    (net (code "78") (name "unconnected-(STM32F401-PA1-Pad15)") (class "Default")
      (node (ref "STM32F401") (pin "15") (pinfunction "PA1_15") (pintype "bidirectional"))
    )
    (net (code "79") (name "unconnected-(STM32F401-PA2-Pad16)") (class "Default")
      (node (ref "STM32F401") (pin "16") (pinfunction "PA2_16") (pintype "bidirectional"))
    )
    (net (code "80") (name "unconnected-(STM32F401-PA3-Pad17)") (class "Default")
      (node (ref "STM32F401") (pin "17") (pinfunction "PA3_17") (pintype "bidirectional"))
    )
    (net (code "81") (name "unconnected-(STM32F401-PA4-Pad20)") (class "Default")
      (node (ref "STM32F401") (pin "20") (pinfunction "PA4_20") (pintype "bidirectional"))
    )
    (net (code "82") (name "unconnected-(STM32F401-PA5-Pad21)") (class "Default")
      (node (ref "STM32F401") (pin "21") (pinfunction "PA5_21") (pintype "bidirectional"))
    )
    (net (code "83") (name "unconnected-(STM32F401-PB5-Pad57)") (class "Default")
      (node (ref "STM32F401") (pin "57") (pinfunction "PB5_57") (pintype "bidirectional"))
    )
    (net (code "84") (name "unconnected-(STM32F401-PB8-Pad61)") (class "Default")
      (node (ref "STM32F401") (pin "61") (pinfunction "PB8_61") (pintype "bidirectional"))
    )
    (net (code "85") (name "unconnected-(STM32F401-PC2-Pad10)") (class "Default")
      (node (ref "STM32F401") (pin "10") (pinfunction "PC2_10") (pintype "bidirectional"))
    )
    (net (code "86") (name "unconnected-(STM32F401-PC14-_OSC32_IN-Pad3)") (class "Default")
      (node (ref "STM32F401") (pin "3") (pinfunction "PC14-_OSC32_IN_3") (pintype "bidirectional"))
    )
    (net (code "87") (name "unconnected-(STM32F401-PC15-_OSC32_OUT-Pad4)") (class "Default")
      (node (ref "STM32F401") (pin "4") (pinfunction "PC15-_OSC32_OUT_4") (pintype "bidirectional"))
    )
    (net (code "88") (name "unconnected-(STM32F401-PH1-_OSC_OUT-Pad6)") (class "Default")
      (node (ref "STM32F401") (pin "6") (pinfunction "PH1-_OSC_OUT_6") (pintype "bidirectional"))
    )
    (net (code "89") (name "unconnected-(STM32F401-VBAT-Pad1)") (class "Default")
      (node (ref "STM32F401") (pin "1") (pinfunction "VBAT_1") (pintype "bidirectional"))
    )
  )
)
